# FLEX_OUTPUTS.net
KiCad netlist of a schematic drawn in Altium Designer
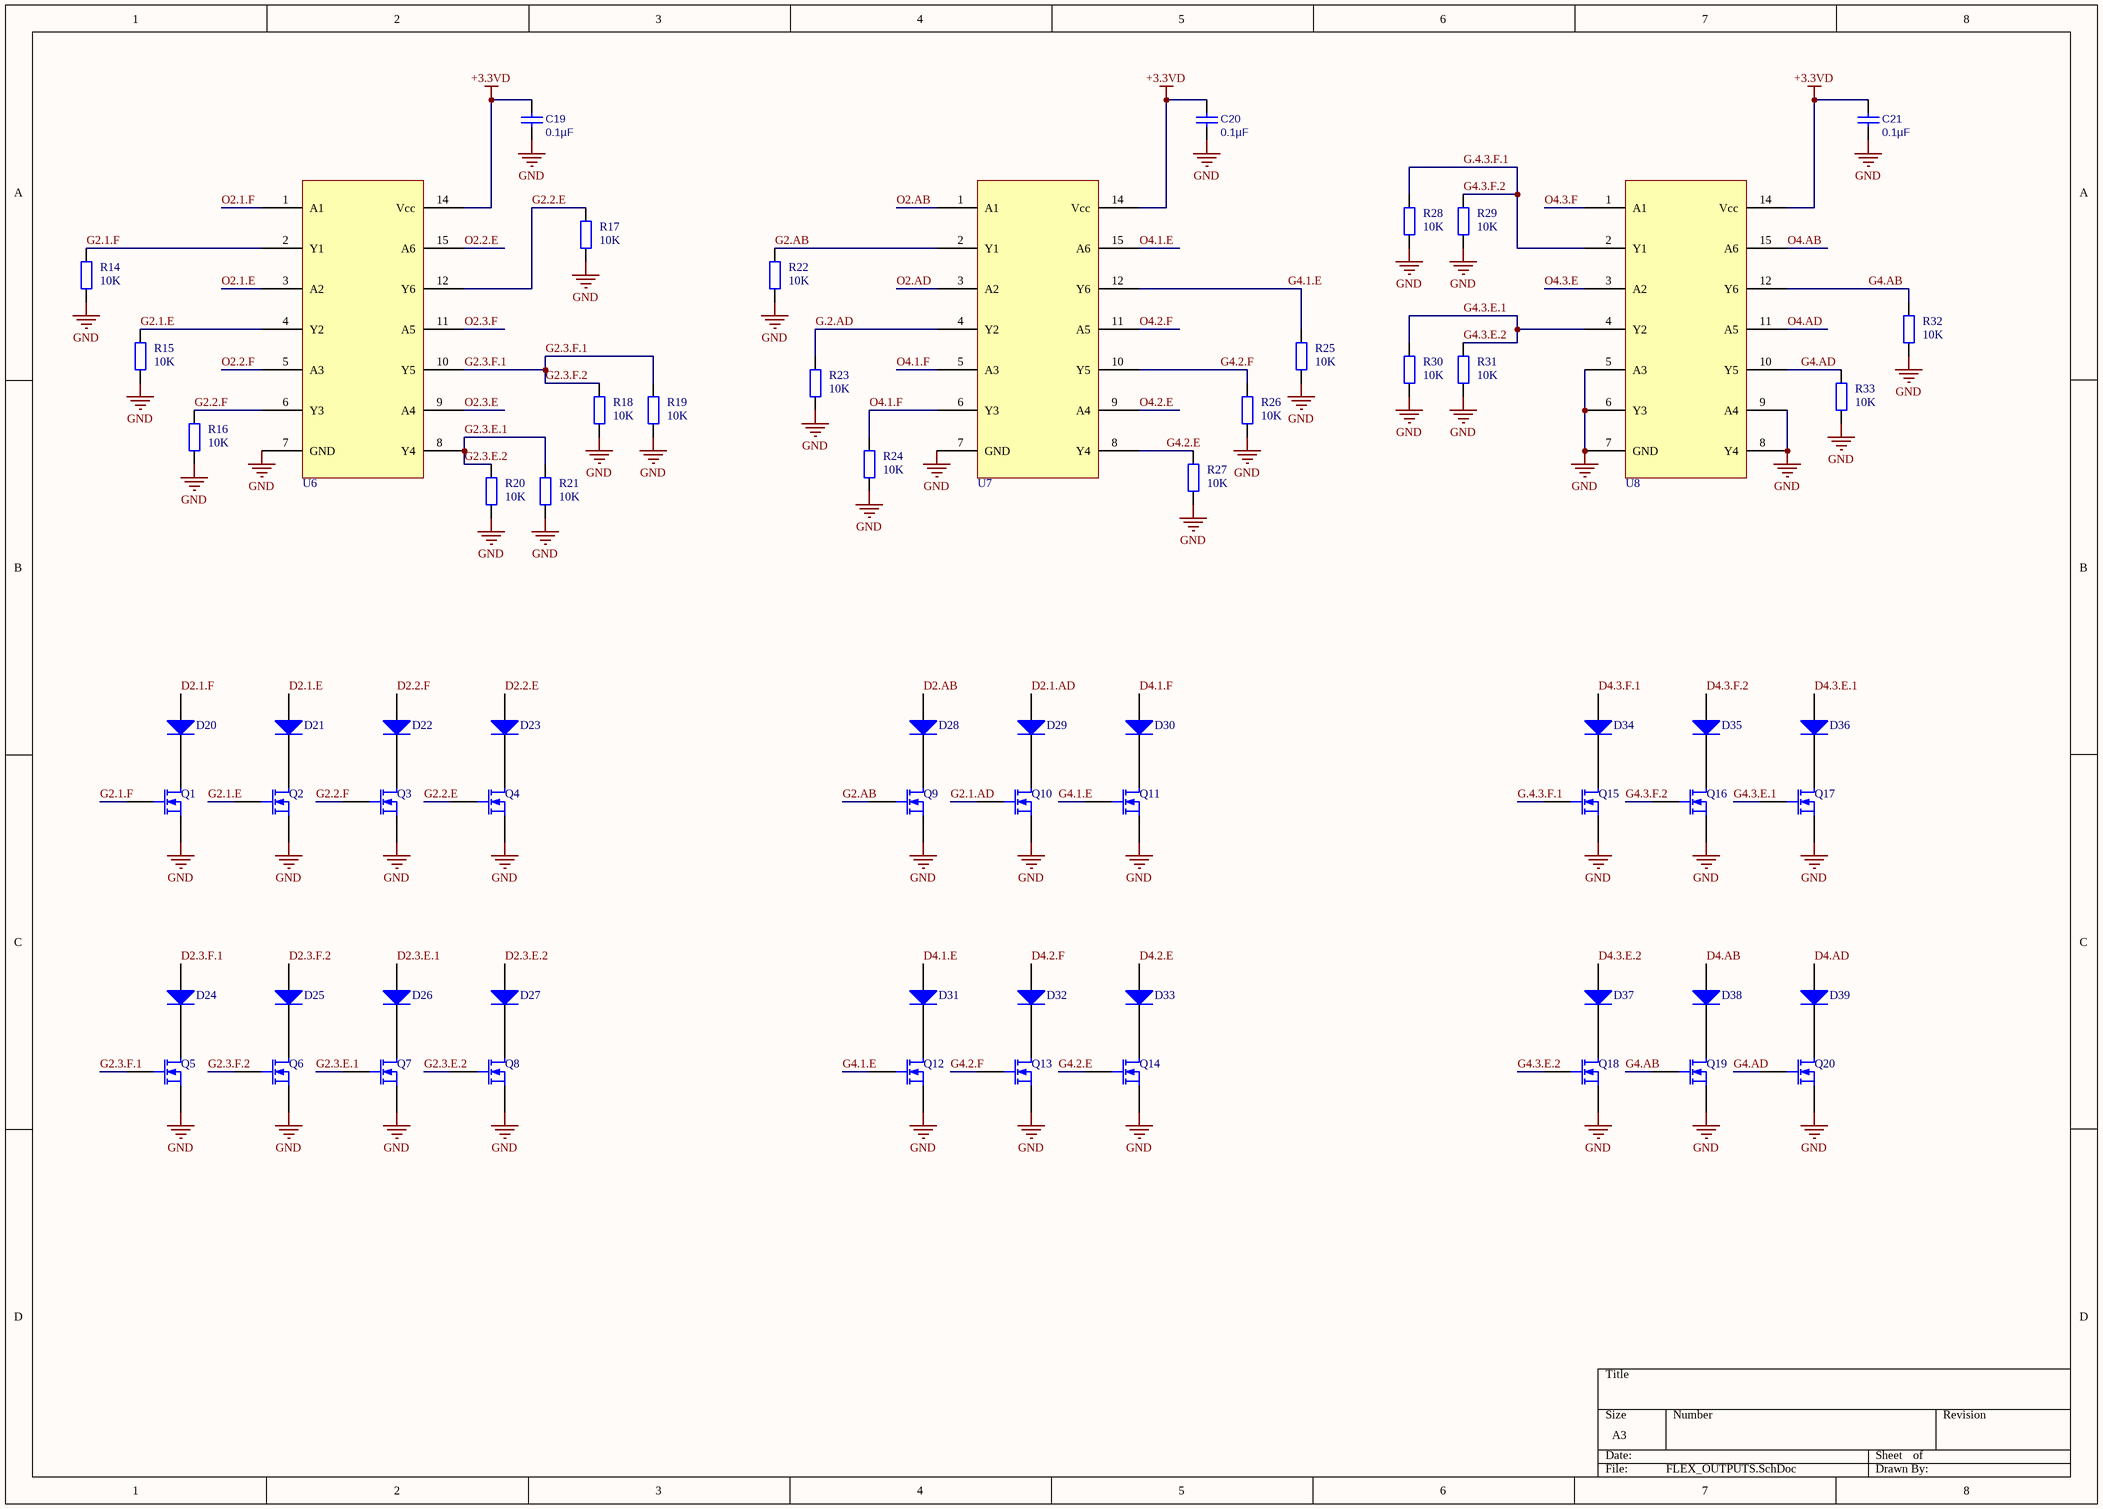
[diagram p0: FLEX_OUTPUTS.SchDoc]

(export (version "E")
  (design (tool "Eeschema 10.0.6"))
  (components
    (comp (ref "C19")
      (value "0.1µF")
      (footprint "TDK C-Series (1608)")
      (description "Capacitor")
      (fields (field (name "Comment") "Cap") (field (name "PUBLISHER") "Altium Limited"))
      (libsource (lib "Miscellaneous Devices") (part "Cap"))
    )
    (comp (ref "C20")
      (value "0.1µF")
      (footprint "TDK C-Series (1608)")
      (description "Capacitor")
      (fields (field (name "Comment") "Cap") (field (name "PUBLISHER") "Altium Limited"))
      (libsource (lib "Miscellaneous Devices") (part "Cap"))
    )
    (comp (ref "C21")
      (value "0.1µF")
      (footprint "TDK C-Series (1608)")
      (description "Capacitor")
      (fields (field (name "Comment") "Cap") (field (name "PUBLISHER") "Altium Limited"))
      (libsource (lib "Miscellaneous Devices") (part "Cap"))
    )
    (comp (ref "D20")
      (value "de")
      (footprint "Diode_Shottky")
      (description "Default Diode")
      (fields (field (name "PUBLISHER") "Altium Limited"))
      (libsource (lib "Miscellaneous Devices") (part "Diode"))
    )
    (comp (ref "D21")
      (value "de")
      (footprint "Diode_Shottky")
      (description "Default Diode")
      (fields (field (name "PUBLISHER") "Altium Limited"))
      (libsource (lib "Miscellaneous Devices") (part "Diode"))
    )
    (comp (ref "D22")
      (value "de")
      (footprint "Diode_Shottky")
      (description "Default Diode")
      (fields (field (name "PUBLISHER") "Altium Limited"))
      (libsource (lib "Miscellaneous Devices") (part "Diode"))
    )
    (comp (ref "D23")
      (value "de")
      (footprint "Diode_Shottky")
      (description "Default Diode")
      (fields (field (name "PUBLISHER") "Altium Limited"))
      (libsource (lib "Miscellaneous Devices") (part "Diode"))
    )
    (comp (ref "D24")
      (value "de")
      (footprint "Diode_Shottky")
      (description "Default Diode")
      (fields (field (name "PUBLISHER") "Altium Limited"))
      (libsource (lib "Miscellaneous Devices") (part "Diode"))
    )
    (comp (ref "D25")
      (value "de")
      (footprint "Diode_Shottky")
      (description "Default Diode")
      (fields (field (name "PUBLISHER") "Altium Limited"))
      (libsource (lib "Miscellaneous Devices") (part "Diode"))
    )
    (comp (ref "D26")
      (value "de")
      (footprint "Diode_Shottky")
      (description "Default Diode")
      (fields (field (name "PUBLISHER") "Altium Limited"))
      (libsource (lib "Miscellaneous Devices") (part "Diode"))
    )
    (comp (ref "D27")
      (value "de")
      (footprint "Diode_Shottky")
      (description "Default Diode")
      (fields (field (name "PUBLISHER") "Altium Limited"))
      (libsource (lib "Miscellaneous Devices") (part "Diode"))
    )
    (comp (ref "D28")
      (value "de")
      (footprint "Diode_Shottky")
      (description "Default Diode")
      (fields (field (name "PUBLISHER") "Altium Limited"))
      (libsource (lib "Miscellaneous Devices") (part "Diode"))
    )
    (comp (ref "D29")
      (value "de")
      (footprint "Diode_Shottky")
      (description "Default Diode")
      (fields (field (name "PUBLISHER") "Altium Limited"))
      (libsource (lib "Miscellaneous Devices") (part "Diode"))
    )
    (comp (ref "D30")
      (value "de")
      (footprint "Diode_Shottky")
      (description "Default Diode")
      (fields (field (name "PUBLISHER") "Altium Limited"))
      (libsource (lib "Miscellaneous Devices") (part "Diode"))
    )
    (comp (ref "D31")
      (value "de")
      (footprint "Diode_Shottky")
      (description "Default Diode")
      (fields (field (name "PUBLISHER") "Altium Limited"))
      (libsource (lib "Miscellaneous Devices") (part "Diode"))
    )
    (comp (ref "D32")
      (value "de")
      (footprint "Diode_Shottky")
      (description "Default Diode")
      (fields (field (name "PUBLISHER") "Altium Limited"))
      (libsource (lib "Miscellaneous Devices") (part "Diode"))
    )
    (comp (ref "D33")
      (value "de")
      (footprint "Diode_Shottky")
      (description "Default Diode")
      (fields (field (name "PUBLISHER") "Altium Limited"))
      (libsource (lib "Miscellaneous Devices") (part "Diode"))
    )
    (comp (ref "D34")
      (value "de")
      (footprint "Diode_Shottky")
      (description "Default Diode")
      (fields (field (name "PUBLISHER") "Altium Limited"))
      (libsource (lib "Miscellaneous Devices") (part "Diode"))
    )
    (comp (ref "D35")
      (value "de")
      (footprint "Diode_Shottky")
      (description "Default Diode")
      (fields (field (name "PUBLISHER") "Altium Limited"))
      (libsource (lib "Miscellaneous Devices") (part "Diode"))
    )
    (comp (ref "D36")
      (value "de")
      (footprint "Diode_Shottky")
      (description "Default Diode")
      (fields (field (name "PUBLISHER") "Altium Limited"))
      (libsource (lib "Miscellaneous Devices") (part "Diode"))
    )
    (comp (ref "D37")
      (value "de")
      (footprint "Diode_Shottky")
      (description "Default Diode")
      (fields (field (name "PUBLISHER") "Altium Limited"))
      (libsource (lib "Miscellaneous Devices") (part "Diode"))
    )
    (comp (ref "D38")
      (value "de")
      (footprint "Diode_Shottky")
      (description "Default Diode")
      (fields (field (name "PUBLISHER") "Altium Limited"))
      (libsource (lib "Miscellaneous Devices") (part "Diode"))
    )
    (comp (ref "D39")
      (value "de")
      (footprint "Diode_Shottky")
      (description "Default Diode")
      (fields (field (name "PUBLISHER") "Altium Limited"))
      (libsource (lib "Miscellaneous Devices") (part "Diode"))
    )
    (comp (ref "Q1")
      (value "~")
      (footprint "MOSFET")
      (description "N-Channel MOSFET")
      (fields (field (name "PUBLISHER") "Altium Limited"))
      (libsource (lib "Miscellaneous Devices") (part "MOSFET-N"))
    )
    (comp (ref "Q2")
      (value "~")
      (footprint "MOSFET")
      (description "N-Channel MOSFET")
      (fields (field (name "PUBLISHER") "Altium Limited"))
      (libsource (lib "Miscellaneous Devices") (part "MOSFET-N"))
    )
    (comp (ref "Q3")
      (value "~")
      (footprint "MOSFET")
      (description "N-Channel MOSFET")
      (fields (field (name "PUBLISHER") "Altium Limited"))
      (libsource (lib "Miscellaneous Devices") (part "MOSFET-N"))
    )
    (comp (ref "Q4")
      (value "~")
      (footprint "MOSFET")
      (description "N-Channel MOSFET")
      (fields (field (name "PUBLISHER") "Altium Limited"))
      (libsource (lib "Miscellaneous Devices") (part "MOSFET-N"))
    )
    (comp (ref "Q5")
      (value "~")
      (footprint "MOSFET")
      (description "N-Channel MOSFET")
      (fields (field (name "PUBLISHER") "Altium Limited"))
      (libsource (lib "Miscellaneous Devices") (part "MOSFET-N"))
    )
    (comp (ref "Q6")
      (value "~")
      (footprint "MOSFET")
      (description "N-Channel MOSFET")
      (fields (field (name "PUBLISHER") "Altium Limited"))
      (libsource (lib "Miscellaneous Devices") (part "MOSFET-N"))
    )
    (comp (ref "Q7")
      (value "~")
      (footprint "MOSFET")
      (description "N-Channel MOSFET")
      (fields (field (name "PUBLISHER") "Altium Limited"))
      (libsource (lib "Miscellaneous Devices") (part "MOSFET-N"))
    )
    (comp (ref "Q8")
      (value "~")
      (footprint "MOSFET")
      (description "N-Channel MOSFET")
      (fields (field (name "PUBLISHER") "Altium Limited"))
      (libsource (lib "Miscellaneous Devices") (part "MOSFET-N"))
    )
    (comp (ref "Q9")
      (value "~")
      (footprint "MOSFET")
      (description "N-Channel MOSFET")
      (fields (field (name "PUBLISHER") "Altium Limited"))
      (libsource (lib "Miscellaneous Devices") (part "MOSFET-N"))
    )
    (comp (ref "Q10")
      (value "~")
      (footprint "MOSFET")
      (description "N-Channel MOSFET")
      (fields (field (name "PUBLISHER") "Altium Limited"))
      (libsource (lib "Miscellaneous Devices") (part "MOSFET-N"))
    )
    (comp (ref "Q11")
      (value "~")
      (footprint "MOSFET")
      (description "N-Channel MOSFET")
      (fields (field (name "PUBLISHER") "Altium Limited"))
      (libsource (lib "Miscellaneous Devices") (part "MOSFET-N"))
    )
    (comp (ref "Q12")
      (value "~")
      (footprint "MOSFET")
      (description "N-Channel MOSFET")
      (fields (field (name "PUBLISHER") "Altium Limited"))
      (libsource (lib "Miscellaneous Devices") (part "MOSFET-N"))
    )
    (comp (ref "Q13")
      (value "~")
      (footprint "MOSFET")
      (description "N-Channel MOSFET")
      (fields (field (name "PUBLISHER") "Altium Limited"))
      (libsource (lib "Miscellaneous Devices") (part "MOSFET-N"))
    )
    (comp (ref "Q14")
      (value "~")
      (footprint "MOSFET")
      (description "N-Channel MOSFET")
      (fields (field (name "PUBLISHER") "Altium Limited"))
      (libsource (lib "Miscellaneous Devices") (part "MOSFET-N"))
    )
    (comp (ref "Q15")
      (value "~")
      (footprint "MOSFET")
      (description "N-Channel MOSFET")
      (fields (field (name "PUBLISHER") "Altium Limited"))
      (libsource (lib "Miscellaneous Devices") (part "MOSFET-N"))
    )
    (comp (ref "Q16")
      (value "~")
      (footprint "MOSFET")
      (description "N-Channel MOSFET")
      (fields (field (name "PUBLISHER") "Altium Limited"))
      (libsource (lib "Miscellaneous Devices") (part "MOSFET-N"))
    )
    (comp (ref "Q17")
      (value "~")
      (footprint "MOSFET")
      (description "N-Channel MOSFET")
      (fields (field (name "PUBLISHER") "Altium Limited"))
      (libsource (lib "Miscellaneous Devices") (part "MOSFET-N"))
    )
    (comp (ref "Q18")
      (value "~")
      (footprint "MOSFET")
      (description "N-Channel MOSFET")
      (fields (field (name "PUBLISHER") "Altium Limited"))
      (libsource (lib "Miscellaneous Devices") (part "MOSFET-N"))
    )
    (comp (ref "Q19")
      (value "~")
      (footprint "MOSFET")
      (description "N-Channel MOSFET")
      (fields (field (name "PUBLISHER") "Altium Limited"))
      (libsource (lib "Miscellaneous Devices") (part "MOSFET-N"))
    )
    (comp (ref "Q20")
      (value "~")
      (footprint "MOSFET")
      (description "N-Channel MOSFET")
      (fields (field (name "PUBLISHER") "Altium Limited"))
      (libsource (lib "Miscellaneous Devices") (part "MOSFET-N"))
    )
    (comp (ref "R14")
      (value "10K")
      (footprint "Panasonic ERJ-Series (1608)")
      (description "Resistor")
      (fields (field (name "PUBLISHER") "Altium Limited"))
      (libsource (lib "Miscellaneous Devices") (part "Res2"))
    )
    (comp (ref "R15")
      (value "10K")
      (footprint "Panasonic ERJ-Series (1608)")
      (description "Resistor")
      (fields (field (name "PUBLISHER") "Altium Limited"))
      (libsource (lib "Miscellaneous Devices") (part "Res2"))
    )
    (comp (ref "R16")
      (value "10K")
      (footprint "Panasonic ERJ-Series (1608)")
      (description "Resistor")
      (fields (field (name "PUBLISHER") "Altium Limited"))
      (libsource (lib "Miscellaneous Devices") (part "Res2"))
    )
    (comp (ref "R17")
      (value "10K")
      (footprint "Panasonic ERJ-Series (1608)")
      (description "Resistor")
      (fields (field (name "PUBLISHER") "Altium Limited"))
      (libsource (lib "Miscellaneous Devices") (part "Res2"))
    )
    (comp (ref "R18")
      (value "10K")
      (footprint "Panasonic ERJ-Series (1608)")
      (description "Resistor")
      (fields (field (name "PUBLISHER") "Altium Limited"))
      (libsource (lib "Miscellaneous Devices") (part "Res2"))
    )
    (comp (ref "R19")
      (value "10K")
      (footprint "Panasonic ERJ-Series (1608)")
      (description "Resistor")
      (fields (field (name "PUBLISHER") "Altium Limited"))
      (libsource (lib "Miscellaneous Devices") (part "Res2"))
    )
    (comp (ref "R20")
      (value "10K")
      (footprint "Panasonic ERJ-Series (1608)")
      (description "Resistor")
      (fields (field (name "PUBLISHER") "Altium Limited"))
      (libsource (lib "Miscellaneous Devices") (part "Res2"))
    )
    (comp (ref "R21")
      (value "10K")
      (footprint "Panasonic ERJ-Series (1608)")
      (description "Resistor")
      (fields (field (name "PUBLISHER") "Altium Limited"))
      (libsource (lib "Miscellaneous Devices") (part "Res2"))
    )
    (comp (ref "R22")
      (value "10K")
      (footprint "Panasonic ERJ-Series (1608)")
      (description "Resistor")
      (fields (field (name "PUBLISHER") "Altium Limited"))
      (libsource (lib "Miscellaneous Devices") (part "Res2"))
    )
    (comp (ref "R23")
      (value "10K")
      (footprint "Panasonic ERJ-Series (1608)")
      (description "Resistor")
      (fields (field (name "PUBLISHER") "Altium Limited"))
      (libsource (lib "Miscellaneous Devices") (part "Res2"))
    )
    (comp (ref "R24")
      (value "10K")
      (footprint "Panasonic ERJ-Series (1608)")
      (description "Resistor")
      (fields (field (name "PUBLISHER") "Altium Limited"))
      (libsource (lib "Miscellaneous Devices") (part "Res2"))
    )
    (comp (ref "R25")
      (value "10K")
      (footprint "Panasonic ERJ-Series (1608)")
      (description "Resistor")
      (fields (field (name "PUBLISHER") "Altium Limited"))
      (libsource (lib "Miscellaneous Devices") (part "Res2"))
    )
    (comp (ref "R26")
      (value "10K")
      (footprint "Panasonic ERJ-Series (1608)")
      (description "Resistor")
      (fields (field (name "PUBLISHER") "Altium Limited"))
      (libsource (lib "Miscellaneous Devices") (part "Res2"))
    )
    (comp (ref "R27")
      (value "10K")
      (footprint "Panasonic ERJ-Series (1608)")
      (description "Resistor")
      (fields (field (name "PUBLISHER") "Altium Limited"))
      (libsource (lib "Miscellaneous Devices") (part "Res2"))
    )
    (comp (ref "R28")
      (value "10K")
      (footprint "Panasonic ERJ-Series (1608)")
      (description "Resistor")
      (fields (field (name "PUBLISHER") "Altium Limited"))
      (libsource (lib "Miscellaneous Devices") (part "Res2"))
    )
    (comp (ref "R29")
      (value "10K")
      (footprint "Panasonic ERJ-Series (1608)")
      (description "Resistor")
      (fields (field (name "PUBLISHER") "Altium Limited"))
      (libsource (lib "Miscellaneous Devices") (part "Res2"))
    )
    (comp (ref "R30")
      (value "10K")
      (footprint "Panasonic ERJ-Series (1608)")
      (description "Resistor")
      (fields (field (name "PUBLISHER") "Altium Limited"))
      (libsource (lib "Miscellaneous Devices") (part "Res2"))
    )
    (comp (ref "R31")
      (value "10K")
      (footprint "Panasonic ERJ-Series (1608)")
      (description "Resistor")
      (fields (field (name "PUBLISHER") "Altium Limited"))
      (libsource (lib "Miscellaneous Devices") (part "Res2"))
    )
    (comp (ref "R32")
      (value "10K")
      (footprint "Panasonic ERJ-Series (1608)")
      (description "Resistor")
      (fields (field (name "PUBLISHER") "Altium Limited"))
      (libsource (lib "Miscellaneous Devices") (part "Res2"))
    )
    (comp (ref "R33")
      (value "10K")
      (footprint "Panasonic ERJ-Series (1608)")
      (description "Resistor")
      (fields (field (name "PUBLISHER") "Altium Limited"))
      (libsource (lib "Miscellaneous Devices") (part "Res2"))
    )
    (comp (ref "U6")
      (value "MC74VHCT50A")
      (description "6-Channel CMOS Buffer")
      (libsource (lib "Schematics Library") (part "MC74VHCT50A"))
    )
    (comp (ref "U7")
      (value "MC74VHCT50A")
      (description "6-Channel CMOS Buffer")
      (libsource (lib "Schematics Library") (part "MC74VHCT50A"))
    )
    (comp (ref "U8")
      (value "MC74VHCT50A")
      (description "6-Channel CMOS Buffer")
      (libsource (lib "Schematics Library") (part "MC74VHCT50A"))
    )
  )
  (nets
    (net (code "1") (name "+3.3VD") (class "Default")
      (node (ref "C19") (pin "2") (pinfunction "2_2") (pintype "passive"))
      (node (ref "C20") (pin "2") (pinfunction "2_2") (pintype "passive"))
      (node (ref "C21") (pin "2") (pinfunction "2_2") (pintype "passive"))
      (node (ref "U6") (pin "14") (pinfunction "Vcc_14") (pintype "power_in"))
      (node (ref "U7") (pin "14") (pinfunction "Vcc_14") (pintype "power_in"))
      (node (ref "U8") (pin "14") (pinfunction "Vcc_14") (pintype "power_in"))
    )
    (net (code "2") (name "/D2.1.AD") (class "Default")
      (node (ref "D29") (pin "1") (pinfunction "A_1") (pintype "passive"))
    )
    (net (code "3") (name "/D2.1.E") (class "Default")
      (node (ref "D21") (pin "1") (pinfunction "A_1") (pintype "passive"))
    )
    (net (code "4") (name "/D2.1.F") (class "Default")
      (node (ref "D20") (pin "1") (pinfunction "A_1") (pintype "passive"))
    )
    (net (code "5") (name "/D2.2.E") (class "Default")
      (node (ref "D23") (pin "1") (pinfunction "A_1") (pintype "passive"))
    )
    (net (code "6") (name "/D2.2.F") (class "Default")
      (node (ref "D22") (pin "1") (pinfunction "A_1") (pintype "passive"))
    )
    (net (code "7") (name "/D2.3.E.1") (class "Default")
      (node (ref "D26") (pin "1") (pinfunction "A_1") (pintype "passive"))
    )
    (net (code "8") (name "/D2.3.E.2") (class "Default")
      (node (ref "D27") (pin "1") (pinfunction "A_1") (pintype "passive"))
    )
    (net (code "9") (name "/D2.3.F.1") (class "Default")
      (node (ref "D24") (pin "1") (pinfunction "A_1") (pintype "passive"))
    )
    (net (code "10") (name "/D2.3.F.2") (class "Default")
      (node (ref "D25") (pin "1") (pinfunction "A_1") (pintype "passive"))
    )
    (net (code "11") (name "/D2.AB") (class "Default")
      (node (ref "D28") (pin "1") (pinfunction "A_1") (pintype "passive"))
    )
    (net (code "12") (name "/D4.1.E") (class "Default")
      (node (ref "D31") (pin "1") (pinfunction "A_1") (pintype "passive"))
    )
    (net (code "13") (name "/D4.1.F") (class "Default")
      (node (ref "D30") (pin "1") (pinfunction "A_1") (pintype "passive"))
    )
    (net (code "14") (name "/D4.2.E") (class "Default")
      (node (ref "D33") (pin "1") (pinfunction "A_1") (pintype "passive"))
    )
    (net (code "15") (name "/D4.2.F") (class "Default")
      (node (ref "D32") (pin "1") (pinfunction "A_1") (pintype "passive"))
    )
    (net (code "16") (name "/D4.3.E.1") (class "Default")
      (node (ref "D36") (pin "1") (pinfunction "A_1") (pintype "passive"))
    )
    (net (code "17") (name "/D4.3.E.2") (class "Default")
      (node (ref "D37") (pin "1") (pinfunction "A_1") (pintype "passive"))
    )
    (net (code "18") (name "/D4.3.F.1") (class "Default")
      (node (ref "D34") (pin "1") (pinfunction "A_1") (pintype "passive"))
    )
    (net (code "19") (name "/D4.3.F.2") (class "Default")
      (node (ref "D35") (pin "1") (pinfunction "A_1") (pintype "passive"))
    )
    (net (code "20") (name "/D4.AB") (class "Default")
      (node (ref "D38") (pin "1") (pinfunction "A_1") (pintype "passive"))
    )
    (net (code "21") (name "/D4.AD") (class "Default")
      (node (ref "D39") (pin "1") (pinfunction "A_1") (pintype "passive"))
    )
    (net (code "22") (name "/G.2.AD") (class "Default")
      (node (ref "R23") (pin "2") (pinfunction "2_2") (pintype "passive"))
      (node (ref "U7") (pin "4") (pinfunction "Y2_4") (pintype "power_in"))
    )
    (net (code "23") (name "/G.4.3.F.1") (class "Default")
      (node (ref "Q15") (pin "2") (pinfunction "G_2") (pintype "passive"))
      (node (ref "Q16") (pin "2") (pinfunction "G_2") (pintype "passive"))
      (node (ref "R28") (pin "2") (pinfunction "2_2") (pintype "passive"))
      (node (ref "R29") (pin "2") (pinfunction "2_2") (pintype "passive"))
      (node (ref "U8") (pin "2") (pinfunction "Y1_2") (pintype "power_in"))
    )
    (net (code "24") (name "/G2.1.AD") (class "Default")
      (node (ref "Q10") (pin "2") (pinfunction "G_2") (pintype "passive"))
    )
    (net (code "25") (name "/G2.1.E") (class "Default")
      (node (ref "Q2") (pin "2") (pinfunction "G_2") (pintype "passive"))
      (node (ref "R15") (pin "2") (pinfunction "2_2") (pintype "passive"))
      (node (ref "U6") (pin "4") (pinfunction "Y2_4") (pintype "power_in"))
    )
    (net (code "26") (name "/G2.1.F") (class "Default")
      (node (ref "Q1") (pin "2") (pinfunction "G_2") (pintype "passive"))
      (node (ref "R14") (pin "2") (pinfunction "2_2") (pintype "passive"))
      (node (ref "U6") (pin "2") (pinfunction "Y1_2") (pintype "power_in"))
    )
    (net (code "27") (name "/G2.2.E") (class "Default")
      (node (ref "Q4") (pin "2") (pinfunction "G_2") (pintype "passive"))
      (node (ref "R17") (pin "2") (pinfunction "2_2") (pintype "passive"))
      (node (ref "U6") (pin "12") (pinfunction "Y6_12") (pintype "power_in"))
    )
    (net (code "28") (name "/G2.2.F") (class "Default")
      (node (ref "Q3") (pin "2") (pinfunction "G_2") (pintype "passive"))
      (node (ref "R16") (pin "2") (pinfunction "2_2") (pintype "passive"))
      (node (ref "U6") (pin "6") (pinfunction "Y3_6") (pintype "power_in"))
    )
    (net (code "29") (name "/G2.3.E.1") (class "Default")
      (node (ref "Q7") (pin "2") (pinfunction "G_2") (pintype "passive"))
      (node (ref "Q8") (pin "2") (pinfunction "G_2") (pintype "passive"))
      (node (ref "R20") (pin "2") (pinfunction "2_2") (pintype "passive"))
      (node (ref "R21") (pin "2") (pinfunction "2_2") (pintype "passive"))
      (node (ref "U6") (pin "8") (pinfunction "Y4_8") (pintype "power_in"))
    )
    (net (code "30") (name "/G2.3.F.1") (class "Default")
      (node (ref "Q5") (pin "2") (pinfunction "G_2") (pintype "passive"))
      (node (ref "Q6") (pin "2") (pinfunction "G_2") (pintype "passive"))
      (node (ref "R18") (pin "2") (pinfunction "2_2") (pintype "passive"))
      (node (ref "R19") (pin "2") (pinfunction "2_2") (pintype "passive"))
      (node (ref "U6") (pin "10") (pinfunction "Y5_10") (pintype "power_in"))
    )
    (net (code "31") (name "/G2.AB") (class "Default")
      (node (ref "Q9") (pin "2") (pinfunction "G_2") (pintype "passive"))
      (node (ref "R22") (pin "2") (pinfunction "2_2") (pintype "passive"))
      (node (ref "U7") (pin "2") (pinfunction "Y1_2") (pintype "power_in"))
    )
    (net (code "32") (name "/G4.1.E") (class "Default")
      (node (ref "Q11") (pin "2") (pinfunction "G_2") (pintype "passive"))
      (node (ref "Q12") (pin "2") (pinfunction "G_2") (pintype "passive"))
      (node (ref "R25") (pin "2") (pinfunction "2_2") (pintype "passive"))
      (node (ref "U7") (pin "12") (pinfunction "Y6_12") (pintype "power_in"))
    )
    (net (code "33") (name "/G4.2.E") (class "Default")
      (node (ref "Q14") (pin "2") (pinfunction "G_2") (pintype "passive"))
      (node (ref "R27") (pin "2") (pinfunction "2_2") (pintype "passive"))
      (node (ref "U7") (pin "8") (pinfunction "Y4_8") (pintype "power_in"))
    )
    (net (code "34") (name "/G4.2.F") (class "Default")
      (node (ref "Q13") (pin "2") (pinfunction "G_2") (pintype "passive"))
      (node (ref "R26") (pin "2") (pinfunction "2_2") (pintype "passive"))
      (node (ref "U7") (pin "10") (pinfunction "Y5_10") (pintype "power_in"))
    )
    (net (code "35") (name "/G4.3.E.1") (class "Default")
      (node (ref "Q17") (pin "2") (pinfunction "G_2") (pintype "passive"))
      (node (ref "Q18") (pin "2") (pinfunction "G_2") (pintype "passive"))
      (node (ref "R30") (pin "2") (pinfunction "2_2") (pintype "passive"))
      (node (ref "R31") (pin "2") (pinfunction "2_2") (pintype "passive"))
      (node (ref "U8") (pin "4") (pinfunction "Y2_4") (pintype "power_in"))
    )
    (net (code "36") (name "/G4.AB") (class "Default")
      (node (ref "Q19") (pin "2") (pinfunction "G_2") (pintype "passive"))
      (node (ref "R32") (pin "2") (pinfunction "2_2") (pintype "passive"))
      (node (ref "U8") (pin "12") (pinfunction "Y6_12") (pintype "power_in"))
    )
    (net (code "37") (name "/G4.AD") (class "Default")
      (node (ref "Q20") (pin "2") (pinfunction "G_2") (pintype "passive"))
      (node (ref "R33") (pin "2") (pinfunction "2_2") (pintype "passive"))
      (node (ref "U8") (pin "10") (pinfunction "Y5_10") (pintype "power_in"))
    )
    (net (code "38") (name "/O2.1.E") (class "Default")
      (node (ref "U6") (pin "3") (pinfunction "A2_3") (pintype "power_in"))
    )
    (net (code "39") (name "/O2.1.F") (class "Default")
      (node (ref "U6") (pin "1") (pinfunction "A1_1") (pintype "power_in"))
    )
    (net (code "40") (name "/O2.2.E") (class "Default")
      (node (ref "U6") (pin "15") (pinfunction "A6_15") (pintype "power_in"))
    )
    (net (code "41") (name "/O2.2.F") (class "Default")
      (node (ref "U6") (pin "5") (pinfunction "A3_5") (pintype "power_in"))
    )
    (net (code "42") (name "/O2.3.E") (class "Default")
      (node (ref "U6") (pin "9") (pinfunction "A4_9") (pintype "power_in"))
    )
    (net (code "43") (name "/O2.3.F") (class "Default")
      (node (ref "U6") (pin "11") (pinfunction "A5_11") (pintype "power_in"))
    )
    (net (code "44") (name "/O2.AB") (class "Default")
      (node (ref "U7") (pin "1") (pinfunction "A1_1") (pintype "power_in"))
    )
    (net (code "45") (name "/O2.AD") (class "Default")
      (node (ref "U7") (pin "3") (pinfunction "A2_3") (pintype "power_in"))
    )
    (net (code "46") (name "/O4.1.E") (class "Default")
      (node (ref "U7") (pin "15") (pinfunction "A6_15") (pintype "power_in"))
    )
    (net (code "47") (name "/O4.1.F") (class "Default")
      (node (ref "R24") (pin "2") (pinfunction "2_2") (pintype "passive"))
      (node (ref "U7") (pin "5") (pinfunction "A3_5") (pintype "power_in"))
      (node (ref "U7") (pin "6") (pinfunction "Y3_6") (pintype "power_in"))
    )
    (net (code "48") (name "/O4.2.E") (class "Default")
      (node (ref "U7") (pin "9") (pinfunction "A4_9") (pintype "power_in"))
    )
    (net (code "49") (name "/O4.2.F") (class "Default")
      (node (ref "U7") (pin "11") (pinfunction "A5_11") (pintype "power_in"))
    )
    (net (code "50") (name "/O4.3.E") (class "Default")
      (node (ref "U8") (pin "3") (pinfunction "A2_3") (pintype "power_in"))
    )
    (net (code "51") (name "/O4.3.F") (class "Default")
      (node (ref "U8") (pin "1") (pinfunction "A1_1") (pintype "power_in"))
    )
    (net (code "52") (name "/O4.AB") (class "Default")
      (node (ref "U8") (pin "15") (pinfunction "A6_15") (pintype "power_in"))
    )
    (net (code "53") (name "/O4.AD") (class "Default")
      (node (ref "U8") (pin "11") (pinfunction "A5_11") (pintype "power_in"))
    )
    (net (code "54") (name "GND") (class "Default")
      (node (ref "C19") (pin "1") (pinfunction "1_1") (pintype "passive"))
      (node (ref "C20") (pin "1") (pinfunction "1_1") (pintype "passive"))
      (node (ref "C21") (pin "1") (pinfunction "1_1") (pintype "passive"))
      (node (ref "Q1") (pin "3") (pinfunction "S_3") (pintype "passive"))
      (node (ref "Q10") (pin "3") (pinfunction "S_3") (pintype "passive"))
      (node (ref "Q11") (pin "3") (pinfunction "S_3") (pintype "passive"))
      (node (ref "Q12") (pin "3") (pinfunction "S_3") (pintype "passive"))
      (node (ref "Q13") (pin "3") (pinfunction "S_3") (pintype "passive"))
      (node (ref "Q14") (pin "3") (pinfunction "S_3") (pintype "passive"))
      (node (ref "Q15") (pin "3") (pinfunction "S_3") (pintype "passive"))
      (node (ref "Q16") (pin "3") (pinfunction "S_3") (pintype "passive"))
      (node (ref "Q17") (pin "3") (pinfunction "S_3") (pintype "passive"))
      (node (ref "Q18") (pin "3") (pinfunction "S_3") (pintype "passive"))
      (node (ref "Q19") (pin "3") (pinfunction "S_3") (pintype "passive"))
      (node (ref "Q2") (pin "3") (pinfunction "S_3") (pintype "passive"))
      (node (ref "Q20") (pin "3") (pinfunction "S_3") (pintype "passive"))
      (node (ref "Q3") (pin "3") (pinfunction "S_3") (pintype "passive"))
      (node (ref "Q4") (pin "3") (pinfunction "S_3") (pintype "passive"))
      (node (ref "Q5") (pin "3") (pinfunction "S_3") (pintype "passive"))
      (node (ref "Q6") (pin "3") (pinfunction "S_3") (pintype "passive"))
      (node (ref "Q7") (pin "3") (pinfunction "S_3") (pintype "passive"))
      (node (ref "Q8") (pin "3") (pinfunction "S_3") (pintype "passive"))
      (node (ref "Q9") (pin "3") (pinfunction "S_3") (pintype "passive"))
      (node (ref "R14") (pin "1") (pinfunction "1_1") (pintype "passive"))
      (node (ref "R15") (pin "1") (pinfunction "1_1") (pintype "passive"))
      (node (ref "R16") (pin "1") (pinfunction "1_1") (pintype "passive"))
      (node (ref "R17") (pin "1") (pinfunction "1_1") (pintype "passive"))
      (node (ref "R18") (pin "1") (pinfunction "1_1") (pintype "passive"))
      (node (ref "R19") (pin "1") (pinfunction "1_1") (pintype "passive"))
      (node (ref "R20") (pin "1") (pinfunction "1_1") (pintype "passive"))
      (node (ref "R21") (pin "1") (pinfunction "1_1") (pintype "passive"))
      (node (ref "R22") (pin "1") (pinfunction "1_1") (pintype "passive"))
      (node (ref "R23") (pin "1") (pinfunction "1_1") (pintype "passive"))
      (node (ref "R24") (pin "1") (pinfunction "1_1") (pintype "passive"))
      (node (ref "R25") (pin "1") (pinfunction "1_1") (pintype "passive"))
      (node (ref "R26") (pin "1") (pinfunction "1_1") (pintype "passive"))
      (node (ref "R27") (pin "1") (pinfunction "1_1") (pintype "passive"))
      (node (ref "R28") (pin "1") (pinfunction "1_1") (pintype "passive"))
      (node (ref "R29") (pin "1") (pinfunction "1_1") (pintype "passive"))
      (node (ref "R30") (pin "1") (pinfunction "1_1") (pintype "passive"))
      (node (ref "R31") (pin "1") (pinfunction "1_1") (pintype "passive"))
      (node (ref "R32") (pin "1") (pinfunction "1_1") (pintype "passive"))
      (node (ref "R33") (pin "1") (pinfunction "1_1") (pintype "passive"))
      (node (ref "U6") (pin "7") (pinfunction "GND_7") (pintype "power_in"))
      (node (ref "U7") (pin "7") (pinfunction "GND_7") (pintype "power_in"))
      (node (ref "U8") (pin "5") (pinfunction "A3_5") (pintype "power_in"))
      (node (ref "U8") (pin "6") (pinfunction "Y3_6") (pintype "power_in"))
      (node (ref "U8") (pin "7") (pinfunction "GND_7") (pintype "power_in"))
      (node (ref "U8") (pin "8") (pinfunction "Y4_8") (pintype "power_in"))
      (node (ref "U8") (pin "9") (pinfunction "A4_9") (pintype "power_in"))
    )
    (net (code "55") (name "Net-(D20-K)") (class "Default")
      (node (ref "D20") (pin "2") (pinfunction "K_2") (pintype "passive"))
      (node (ref "Q1") (pin "1") (pinfunction "D_1") (pintype "passive"))
    )
    (net (code "56") (name "Net-(D21-K)") (class "Default")
      (node (ref "D21") (pin "2") (pinfunction "K_2") (pintype "passive"))
      (node (ref "Q2") (pin "1") (pinfunction "D_1") (pintype "passive"))
    )
    (net (code "57") (name "Net-(D22-K)") (class "Default")
      (node (ref "D22") (pin "2") (pinfunction "K_2") (pintype "passive"))
      (node (ref "Q3") (pin "1") (pinfunction "D_1") (pintype "passive"))
    )
    (net (code "58") (name "Net-(D23-K)") (class "Default")
      (node (ref "D23") (pin "2") (pinfunction "K_2") (pintype "passive"))
      (node (ref "Q4") (pin "1") (pinfunction "D_1") (pintype "passive"))
    )
    (net (code "59") (name "Net-(D24-K)") (class "Default")
      (node (ref "D24") (pin "2") (pinfunction "K_2") (pintype "passive"))
      (node (ref "Q5") (pin "1") (pinfunction "D_1") (pintype "passive"))
    )
    (net (code "60") (name "Net-(D25-K)") (class "Default")
      (node (ref "D25") (pin "2") (pinfunction "K_2") (pintype "passive"))
      (node (ref "Q6") (pin "1") (pinfunction "D_1") (pintype "passive"))
    )
    (net (code "61") (name "Net-(D26-K)") (class "Default")
      (node (ref "D26") (pin "2") (pinfunction "K_2") (pintype "passive"))
      (node (ref "Q7") (pin "1") (pinfunction "D_1") (pintype "passive"))
    )
    (net (code "62") (name "Net-(D27-K)") (class "Default")
      (node (ref "D27") (pin "2") (pinfunction "K_2") (pintype "passive"))
      (node (ref "Q8") (pin "1") (pinfunction "D_1") (pintype "passive"))
    )
    (net (code "63") (name "Net-(D28-K)") (class "Default")
      (node (ref "D28") (pin "2") (pinfunction "K_2") (pintype "passive"))
      (node (ref "Q9") (pin "1") (pinfunction "D_1") (pintype "passive"))
    )
    (net (code "64") (name "Net-(D29-K)") (class "Default")
      (node (ref "D29") (pin "2") (pinfunction "K_2") (pintype "passive"))
      (node (ref "Q10") (pin "1") (pinfunction "D_1") (pintype "passive"))
    )
    (net (code "65") (name "Net-(D30-K)") (class "Default")
      (node (ref "D30") (pin "2") (pinfunction "K_2") (pintype "passive"))
      (node (ref "Q11") (pin "1") (pinfunction "D_1") (pintype "passive"))
    )
    (net (code "66") (name "Net-(D31-K)") (class "Default")
      (node (ref "D31") (pin "2") (pinfunction "K_2") (pintype "passive"))
      (node (ref "Q12") (pin "1") (pinfunction "D_1") (pintype "passive"))
    )
    (net (code "67") (name "Net-(D32-K)") (class "Default")
      (node (ref "D32") (pin "2") (pinfunction "K_2") (pintype "passive"))
      (node (ref "Q13") (pin "1") (pinfunction "D_1") (pintype "passive"))
    )
    (net (code "68") (name "Net-(D33-K)") (class "Default")
      (node (ref "D33") (pin "2") (pinfunction "K_2") (pintype "passive"))
      (node (ref "Q14") (pin "1") (pinfunction "D_1") (pintype "passive"))
    )
    (net (code "69") (name "Net-(D34-K)") (class "Default")
      (node (ref "D34") (pin "2") (pinfunction "K_2") (pintype "passive"))
      (node (ref "Q15") (pin "1") (pinfunction "D_1") (pintype "passive"))
    )
    (net (code "70") (name "Net-(D35-K)") (class "Default")
      (node (ref "D35") (pin "2") (pinfunction "K_2") (pintype "passive"))
      (node (ref "Q16") (pin "1") (pinfunction "D_1") (pintype "passive"))
    )
    (net (code "71") (name "Net-(D36-K)") (class "Default")
      (node (ref "D36") (pin "2") (pinfunction "K_2") (pintype "passive"))
      (node (ref "Q17") (pin "1") (pinfunction "D_1") (pintype "passive"))
    )
    (net (code "72") (name "Net-(D37-K)") (class "Default")
      (node (ref "D37") (pin "2") (pinfunction "K_2") (pintype "passive"))
      (node (ref "Q18") (pin "1") (pinfunction "D_1") (pintype "passive"))
    )
    (net (code "73") (name "Net-(D38-K)") (class "Default")
      (node (ref "D38") (pin "2") (pinfunction "K_2") (pintype "passive"))
      (node (ref "Q19") (pin "1") (pinfunction "D_1") (pintype "passive"))
    )
    (net (code "74") (name "Net-(D39-K)") (class "Default")
      (node (ref "D39") (pin "2") (pinfunction "K_2") (pintype "passive"))
      (node (ref "Q20") (pin "1") (pinfunction "D_1") (pintype "passive"))
    )
  )
)
